# 12V_Converter.net
KiCad netlist of a schematic drawn in Altium Designer
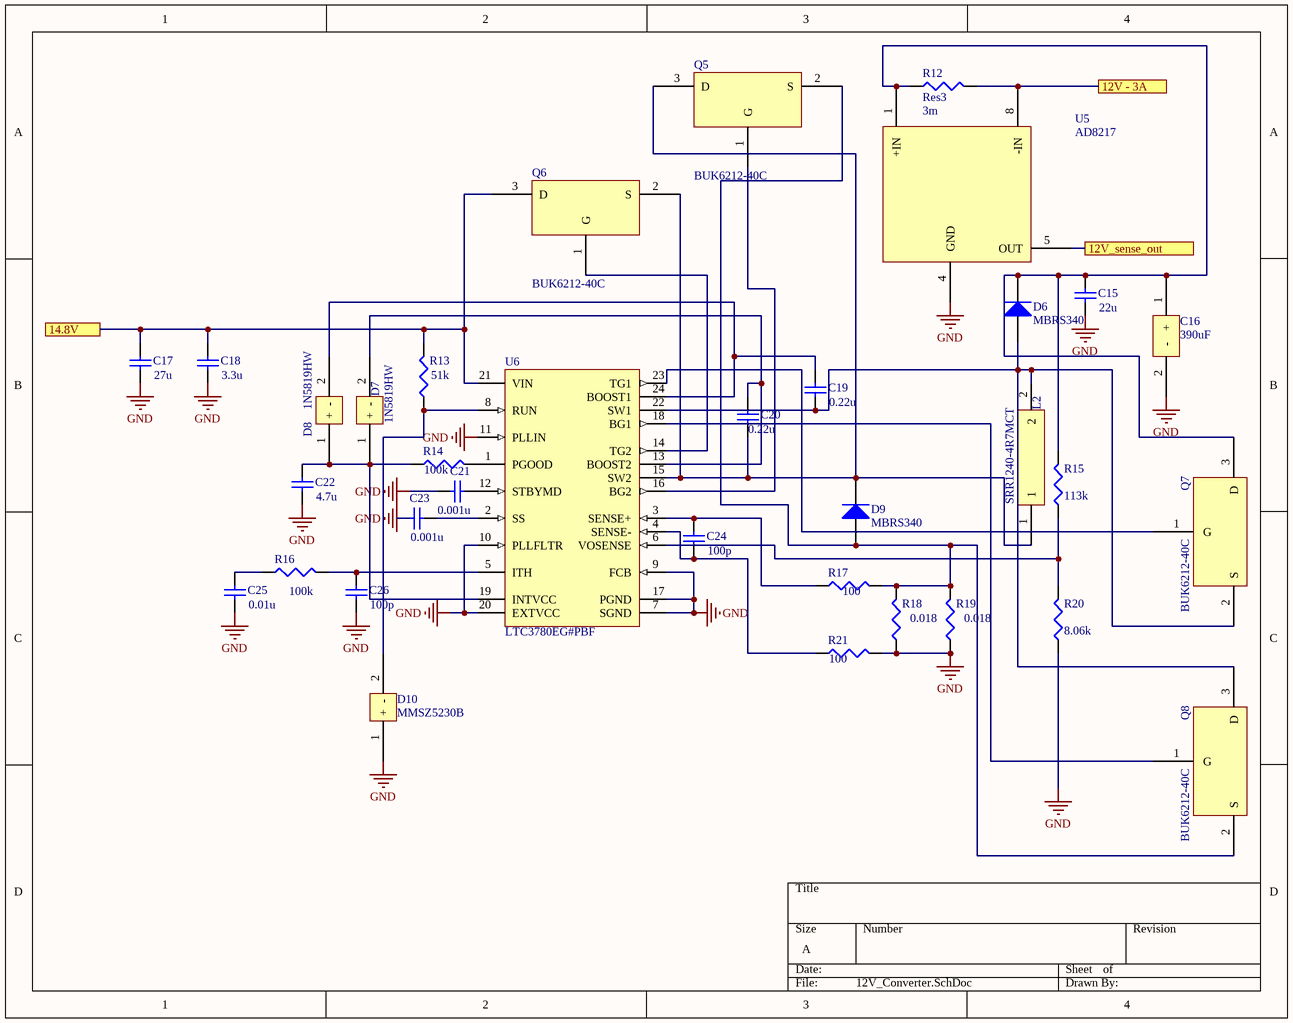
[diagram p0: 12V_Converter.SchDoc]

(export (version "E")
  (design (tool "Eeschema 10.0.6"))
  (components
    (comp (ref "C15")
      (value "22u")
      (footprint "C1206")
      (description "Capacitor (Semiconductor SIM Model)")
      (fields (field (name "Comment") "Cap Semi") (field (name "PUBLISHER") "Altium Limited"))
      (libsource (lib "Miscellaneous Devices") (part "Cap Semi"))
    )
    (comp (ref "C16")
      (value "390uF")
      (footprint "PCV1E391MCL2GS")
      (description "Aluminum Capacitor")
      (libsource (lib "Integrated_Library") (part "PCV1E391MCL2GS"))
    )
    (comp (ref "C17")
      (value "27u")
      (footprint "C1206")
      (description "Capacitor (Semiconductor SIM Model)")
      (fields (field (name "Comment") "Cap Semi") (field (name "PUBLISHER") "Altium Limited"))
      (libsource (lib "Miscellaneous Devices") (part "Cap Semi"))
    )
    (comp (ref "C18")
      (value "3.3u")
      (footprint "C1206")
      (description "Capacitor (Semiconductor SIM Model)")
      (fields (field (name "Comment") "Cap Semi") (field (name "PUBLISHER") "Altium Limited"))
      (libsource (lib "Miscellaneous Devices") (part "Cap Semi"))
    )
    (comp (ref "C19")
      (value "0.22u")
      (footprint "C1206")
      (description "Capacitor (Semiconductor SIM Model)")
      (fields (field (name "Comment") "Cap Semi") (field (name "PUBLISHER") "Altium Limited"))
      (libsource (lib "Miscellaneous Devices") (part "Cap Semi"))
    )
    (comp (ref "C20")
      (value "0.22u")
      (footprint "C1206")
      (description "Capacitor (Semiconductor SIM Model)")
      (fields (field (name "Comment") "Cap Semi") (field (name "PUBLISHER") "Altium Limited"))
      (libsource (lib "Miscellaneous Devices") (part "Cap Semi"))
    )
    (comp (ref "C21")
      (value "0.001u")
      (footprint "C1206")
      (description "Capacitor (Semiconductor SIM Model)")
      (fields (field (name "Comment") "Cap Semi") (field (name "PUBLISHER") "Altium Limited"))
      (libsource (lib "Miscellaneous Devices") (part "Cap Semi"))
    )
    (comp (ref "C22")
      (value "4.7u")
      (footprint "C1206")
      (description "Capacitor (Semiconductor SIM Model)")
      (fields (field (name "Comment") "Cap Semi") (field (name "PUBLISHER") "Altium Limited"))
      (libsource (lib "Miscellaneous Devices") (part "Cap Semi"))
    )
    (comp (ref "C23")
      (value "0.001u")
      (footprint "C1206")
      (description "Capacitor (Semiconductor SIM Model)")
      (fields (field (name "Comment") "Cap Semi") (field (name "PUBLISHER") "Altium Limited"))
      (libsource (lib "Miscellaneous Devices") (part "Cap Semi"))
    )
    (comp (ref "C24")
      (value "100p")
      (footprint "C1206")
      (description "Capacitor (Semiconductor SIM Model)")
      (fields (field (name "Comment") "Cap Semi") (field (name "PUBLISHER") "Altium Limited"))
      (libsource (lib "Miscellaneous Devices") (part "Cap Semi"))
    )
    (comp (ref "C25")
      (value "0.01u")
      (footprint "C1206")
      (description "Capacitor (Semiconductor SIM Model)")
      (fields (field (name "Comment") "Cap Semi") (field (name "PUBLISHER") "Altium Limited"))
      (libsource (lib "Miscellaneous Devices") (part "Cap Semi"))
    )
    (comp (ref "C26")
      (value "100p")
      (footprint "C1206")
      (description "Capacitor (Semiconductor SIM Model)")
      (fields (field (name "Comment") "Cap Semi") (field (name "PUBLISHER") "Altium Limited"))
      (libsource (lib "Miscellaneous Devices") (part "Cap Semi"))
    )
    (comp (ref "D6")
      (value "MBRS340")
      (footprint "SMC")
      (description "Default Diode")
      (fields (field (name "PUBLISHER") "Altium Limited"))
      (libsource (lib "Miscellaneous Devices") (part "Diode"))
    )
    (comp (ref "D7")
      (value "1N5819HW")
      (footprint "1N5819HW")
      (description "1A Schottky Barrier Rectifier")
      (libsource (lib "Integrated_Library") (part "1N5819HW"))
    )
    (comp (ref "D8")
      (value "1N5819HW")
      (footprint "1N5819HW")
      (description "1A Schottky Barrier Rectifier")
      (libsource (lib "Integrated_Library") (part "1N5819HW"))
    )
    (comp (ref "D9")
      (value "MBRS340")
      (footprint "SMC")
      (description "Default Diode")
      (fields (field (name "PUBLISHER") "Altium Limited"))
      (libsource (lib "Miscellaneous Devices") (part "Diode"))
    )
    (comp (ref "D10")
      (value "MMSZ5230B")
      (footprint "MMSZ5230B")
      (description "Zener Diode")
      (libsource (lib "Integrated_Library") (part "MMSZ5230B"))
    )
    (comp (ref "L2")
      (value "SRR1240-4R7MCT")
      (footprint "SRR1240-4R7M")
      (description "Inductor")
      (libsource (lib "Integrated_Library") (part "SRR1240-4R7MCT"))
    )
    (comp (ref "Q5")
      (value "BUK6212-40C")
      (footprint "BUK6212-40C")
      (description "N-Channel TrenchMOS Intermediate Level FET")
      (libsource (lib "") (part "BUK6212-40C_1"))
    )
    (comp (ref "Q6")
      (value "BUK6212-40C")
      (footprint "BUK6212-40C")
      (description "N-Channel TrenchMOS Intermediate Level FET")
      (libsource (lib "") (part "BUK6212-40C_1"))
    )
    (comp (ref "Q7")
      (value "BUK6212-40C")
      (footprint "BUK6212-40C")
      (description "N-Channel TrenchMOS Intermediate Level FET")
      (libsource (lib "Integrated_Library") (part "BUK6212-40C"))
    )
    (comp (ref "Q8")
      (value "BUK6212-40C")
      (footprint "BUK6212-40C")
      (description "N-Channel TrenchMOS Intermediate Level FET")
      (libsource (lib "Integrated_Library") (part "BUK6212-40C"))
    )
    (comp (ref "R12")
      (value "Res3")
      (footprint "14-1210")
      (description "Resistor")
      (fields (field (name "ALTIUM_VALUE") "3m") (field (name "PUBLISHER") "Altium Limited"))
      (libsource (lib "Miscellaneous Devices") (part "Res3"))
    )
    (comp (ref "R13")
      (value "51k")
      (footprint "J1-0603")
      (description "Resistor")
      (fields (field (name "Comment") "Res3") (field (name "PUBLISHER") "Altium Limited"))
      (libsource (lib "Miscellaneous Devices") (part "Res3"))
    )
    (comp (ref "R14")
      (value "100k")
      (footprint "J1-0603")
      (description "Resistor")
      (fields (field (name "Comment") "Res3") (field (name "PUBLISHER") "Altium Limited"))
      (libsource (lib "Miscellaneous Devices") (part "Res3"))
    )
    (comp (ref "R15")
      (value "113k")
      (footprint "J1-0603")
      (description "Resistor")
      (fields (field (name "Comment") "Res3") (field (name "PUBLISHER") "Altium Limited"))
      (libsource (lib "Miscellaneous Devices") (part "Res3"))
    )
    (comp (ref "R16")
      (value "100k")
      (footprint "J1-0603")
      (description "Resistor")
      (fields (field (name "Comment") "Res3") (field (name "PUBLISHER") "Altium Limited"))
      (libsource (lib "Miscellaneous Devices") (part "Res3"))
    )
    (comp (ref "R17")
      (value "100")
      (footprint "J1-0603")
      (description "Resistor")
      (fields (field (name "Comment") "Res3") (field (name "PUBLISHER") "Altium Limited"))
      (libsource (lib "Miscellaneous Devices") (part "Res3"))
    )
    (comp (ref "R18")
      (value "0.018")
      (footprint "14-1210")
      (description "Resistor")
      (fields (field (name "Comment") "Res3") (field (name "PUBLISHER") "Altium Limited"))
      (libsource (lib "Miscellaneous Devices") (part "Res3"))
    )
    (comp (ref "R19")
      (value "0.018")
      (footprint "14-1210")
      (description "Resistor")
      (fields (field (name "Comment") "Res3") (field (name "PUBLISHER") "Altium Limited"))
      (libsource (lib "Miscellaneous Devices") (part "Res3"))
    )
    (comp (ref "R20")
      (value "8.06k")
      (footprint "J1-0603")
      (description "Resistor")
      (fields (field (name "Comment") "Res3") (field (name "PUBLISHER") "Altium Limited"))
      (libsource (lib "Miscellaneous Devices") (part "Res3"))
    )
    (comp (ref "R21")
      (value "100")
      (footprint "J1-0603")
      (description "Resistor")
      (fields (field (name "Comment") "Res3") (field (name "PUBLISHER") "Altium Limited"))
      (libsource (lib "Miscellaneous Devices") (part "Res3"))
    )
    (comp (ref "U5")
      (value "AD8217")
      (footprint "AD8217")
      (description "Current Shunt Moniter")
      (libsource (lib "Integrated_Library") (part "AD8217"))
    )
    (comp (ref "U6")
      (value "LTC3780EG#PBF")
      (footprint "LTC3780 24-Leaqd Plastic SSOP")
      (fields (field (name "MANUFACTURER") "Linear Technology"))
      (libsource (lib "Integrated_Library") (part "LTC3780EG#PBF"))
    )
  )
  (nets
    (net (code "1") (name "/12V - 3A") (class "Default")
      (node (ref "R12") (pin "2") (pinfunction "2_2") (pintype "passive"))
      (node (ref "U5") (pin "8") (pinfunction "-IN_8") (pintype "passive"))
    )
    (net (code "2") (name "/12V_sense_out") (class "Default")
      (node (ref "U5") (pin "5") (pinfunction "OUT_5") (pintype "passive"))
    )
    (net (code "3") (name "/14.8V") (class "Default")
      (node (ref "C17") (pin "2") (pinfunction "2_2") (pintype "passive"))
      (node (ref "C18") (pin "2") (pinfunction "2_2") (pintype "passive"))
      (node (ref "Q6") (pin "3") (pinfunction "D_3") (pintype "passive"))
      (node (ref "R13") (pin "2") (pinfunction "2_2") (pintype "passive"))
      (node (ref "U6") (pin "21") (pinfunction "VIN_21") (pintype "power_in"))
    )
    (net (code "4") (name "GND") (class "Default")
      (node (ref "C15") (pin "1") (pinfunction "1_1") (pintype "passive"))
      (node (ref "C16") (pin "2") (pinfunction "-_2") (pintype "passive"))
      (node (ref "C17") (pin "1") (pinfunction "1_1") (pintype "passive"))
      (node (ref "C18") (pin "1") (pinfunction "1_1") (pintype "passive"))
      (node (ref "C21") (pin "1") (pinfunction "1_1") (pintype "passive"))
      (node (ref "C22") (pin "1") (pinfunction "1_1") (pintype "passive"))
      (node (ref "C23") (pin "1") (pinfunction "1_1") (pintype "passive"))
      (node (ref "C25") (pin "1") (pinfunction "1_1") (pintype "passive"))
      (node (ref "C26") (pin "1") (pinfunction "1_1") (pintype "passive"))
      (node (ref "D10") (pin "1") (pinfunction "+_1") (pintype "passive"))
      (node (ref "R18") (pin "1") (pinfunction "1_1") (pintype "passive"))
      (node (ref "R19") (pin "1") (pinfunction "1_1") (pintype "passive"))
      (node (ref "R20") (pin "1") (pinfunction "1_1") (pintype "passive"))
      (node (ref "R21") (pin "2") (pinfunction "2_2") (pintype "passive"))
      (node (ref "U5") (pin "4") (pinfunction "GND_4") (pintype "passive"))
      (node (ref "U6") (pin "10") (pinfunction "PLLFLTR_10") (pintype "input"))
      (node (ref "U6") (pin "11") (pinfunction "PLLIN_11") (pintype "input"))
      (node (ref "U6") (pin "17") (pinfunction "PGND_17") (pintype "power_in"))
      (node (ref "U6") (pin "20") (pinfunction "EXTVCC_20") (pintype "power_in"))
      (node (ref "U6") (pin "7") (pinfunction "SGND_7") (pintype "power_in"))
      (node (ref "U6") (pin "9") (pinfunction "FCB_9") (pintype "input"))
    )
    (net (code "5") (name "Net-(C16-+)") (class "Default")
      (node (ref "C15") (pin "2") (pinfunction "2_2") (pintype "passive"))
      (node (ref "C16") (pin "1") (pinfunction "+_1") (pintype "passive"))
      (node (ref "D6") (pin "2") (pinfunction "K_2") (pintype "passive"))
      (node (ref "Q7") (pin "3") (pinfunction "D_3") (pintype "passive"))
      (node (ref "R12") (pin "1") (pinfunction "1_1") (pintype "passive"))
      (node (ref "R15") (pin "2") (pinfunction "2_2") (pintype "passive"))
      (node (ref "U5") (pin "1") (pinfunction "+IN_1") (pintype "passive"))
    )
    (net (code "6") (name "Net-(C25-Pad2)") (class "Default")
      (node (ref "C25") (pin "2") (pinfunction "2_2") (pintype "passive"))
      (node (ref "R16") (pin "1") (pinfunction "1_1") (pintype "passive"))
    )
    (net (code "7") (name "Net-(D6-A)") (class "Default")
      (node (ref "C19") (pin "1") (pinfunction "1_1") (pintype "passive"))
      (node (ref "D6") (pin "1") (pinfunction "A_1") (pintype "passive"))
      (node (ref "L2") (pin "2") (pinfunction "2_2") (pintype "passive"))
      (node (ref "Q7") (pin "2") (pinfunction "S_2") (pintype "passive"))
      (node (ref "Q8") (pin "3") (pinfunction "D_3") (pintype "passive"))
      (node (ref "U6") (pin "22") (pinfunction "SW1_22") (pintype "passive"))
    )
    (net (code "8") (name "Net-(D7-+)") (class "Default")
      (node (ref "C22") (pin "2") (pinfunction "2_2") (pintype "passive"))
      (node (ref "D7") (pin "1") (pinfunction "+_1") (pintype "passive"))
      (node (ref "D8") (pin "1") (pinfunction "+_1") (pintype "passive"))
      (node (ref "R14") (pin "1") (pinfunction "1_1") (pintype "passive"))
      (node (ref "U6") (pin "19") (pinfunction "INTVCC_19") (pintype "power_in"))
    )
    (net (code "9") (name "Net-(D7--)") (class "Default")
      (node (ref "C20") (pin "2") (pinfunction "2_2") (pintype "passive"))
      (node (ref "D7") (pin "2") (pinfunction "-_2") (pintype "passive"))
      (node (ref "U6") (pin "13") (pinfunction "BOOST2_13") (pintype "passive"))
    )
    (net (code "10") (name "Net-(D8--)") (class "Default")
      (node (ref "C19") (pin "2") (pinfunction "2_2") (pintype "passive"))
      (node (ref "D8") (pin "2") (pinfunction "-_2") (pintype "passive"))
      (node (ref "U6") (pin "24") (pinfunction "BOOST1_24") (pintype "passive"))
    )
    (net (code "11") (name "Net-(D9-A)") (class "Default")
      (node (ref "D9") (pin "1") (pinfunction "A_1") (pintype "passive"))
      (node (ref "Q5") (pin "2") (pinfunction "S_2") (pintype "passive"))
      (node (ref "Q8") (pin "2") (pinfunction "S_2") (pintype "passive"))
      (node (ref "R17") (pin "2") (pinfunction "2_2") (pintype "passive"))
      (node (ref "R18") (pin "2") (pinfunction "2_2") (pintype "passive"))
      (node (ref "R19") (pin "2") (pinfunction "2_2") (pintype "passive"))
    )
    (net (code "12") (name "Net-(D9-K)") (class "Default")
      (node (ref "C20") (pin "1") (pinfunction "1_1") (pintype "passive"))
      (node (ref "D9") (pin "2") (pinfunction "K_2") (pintype "passive"))
      (node (ref "L2") (pin "1") (pinfunction "1_1") (pintype "passive"))
      (node (ref "Q5") (pin "3") (pinfunction "D_3") (pintype "passive"))
      (node (ref "Q6") (pin "2") (pinfunction "S_2") (pintype "passive"))
      (node (ref "U6") (pin "15") (pinfunction "SW2_15") (pintype "passive"))
    )
    (net (code "13") (name "Net-(D10--)") (class "Default")
      (node (ref "D10") (pin "2") (pinfunction "-_2") (pintype "passive"))
      (node (ref "R13") (pin "1") (pinfunction "1_1") (pintype "passive"))
      (node (ref "U6") (pin "8") (pinfunction "RUN_8") (pintype "input"))
    )
    (net (code "14") (name "Net-(Q5-G)") (class "Default")
      (node (ref "Q5") (pin "1") (pinfunction "G_1") (pintype "passive"))
      (node (ref "U6") (pin "16") (pinfunction "BG2_16") (pintype "output"))
    )
    (net (code "15") (name "Net-(Q6-G)") (class "Default")
      (node (ref "Q6") (pin "1") (pinfunction "G_1") (pintype "passive"))
      (node (ref "U6") (pin "14") (pinfunction "TG2_14") (pintype "output"))
    )
    (net (code "16") (name "Net-(Q7-G)") (class "Default")
      (node (ref "Q7") (pin "1") (pinfunction "G_1") (pintype "passive"))
      (node (ref "U6") (pin "23") (pinfunction "TG1_23") (pintype "output"))
    )
    (net (code "17") (name "Net-(Q8-G)") (class "Default")
      (node (ref "Q8") (pin "1") (pinfunction "G_1") (pintype "passive"))
      (node (ref "U6") (pin "18") (pinfunction "BG1_18") (pintype "output"))
    )
    (net (code "18") (name "Net-(U6-ITH)") (class "Default")
      (node (ref "C26") (pin "2") (pinfunction "2_2") (pintype "passive"))
      (node (ref "R16") (pin "2") (pinfunction "2_2") (pintype "passive"))
      (node (ref "U6") (pin "5") (pinfunction "ITH_5") (pintype "passive"))
    )
    (net (code "19") (name "Net-(U6-PGOOD)") (class "Default")
      (node (ref "R14") (pin "2") (pinfunction "2_2") (pintype "passive"))
      (node (ref "U6") (pin "1") (pinfunction "PGOOD_1") (pintype "open_collector"))
    )
    (net (code "20") (name "Net-(U6-SENSE+)") (class "Default")
      (node (ref "C24") (pin "2") (pinfunction "2_2") (pintype "passive"))
      (node (ref "R17") (pin "1") (pinfunction "1_1") (pintype "passive"))
      (node (ref "U6") (pin "3") (pinfunction "SENSE+_3") (pintype "input"))
    )
    (net (code "21") (name "Net-(U6-SENSE-)") (class "Default")
      (node (ref "C24") (pin "1") (pinfunction "1_1") (pintype "passive"))
      (node (ref "R21") (pin "1") (pinfunction "1_1") (pintype "passive"))
      (node (ref "U6") (pin "4") (pinfunction "SENSE-_4") (pintype "input"))
    )
    (net (code "22") (name "Net-(U6-SS)") (class "Default")
      (node (ref "C23") (pin "2") (pinfunction "2_2") (pintype "passive"))
      (node (ref "U6") (pin "2") (pinfunction "SS_2") (pintype "input"))
    )
    (net (code "23") (name "Net-(U6-STBYMD)") (class "Default")
      (node (ref "C21") (pin "2") (pinfunction "2_2") (pintype "passive"))
      (node (ref "U6") (pin "12") (pinfunction "STBYMD_12") (pintype "input"))
    )
    (net (code "24") (name "Net-(U6-VOSENSE)") (class "Default")
      (node (ref "R15") (pin "1") (pinfunction "1_1") (pintype "passive"))
      (node (ref "R20") (pin "2") (pinfunction "2_2") (pintype "passive"))
      (node (ref "U6") (pin "6") (pinfunction "VOSENSE_6") (pintype "input"))
    )
  )
)
